# uart_rs232_adapter.net
KiCad netlist of a schematic drawn in EAGLE
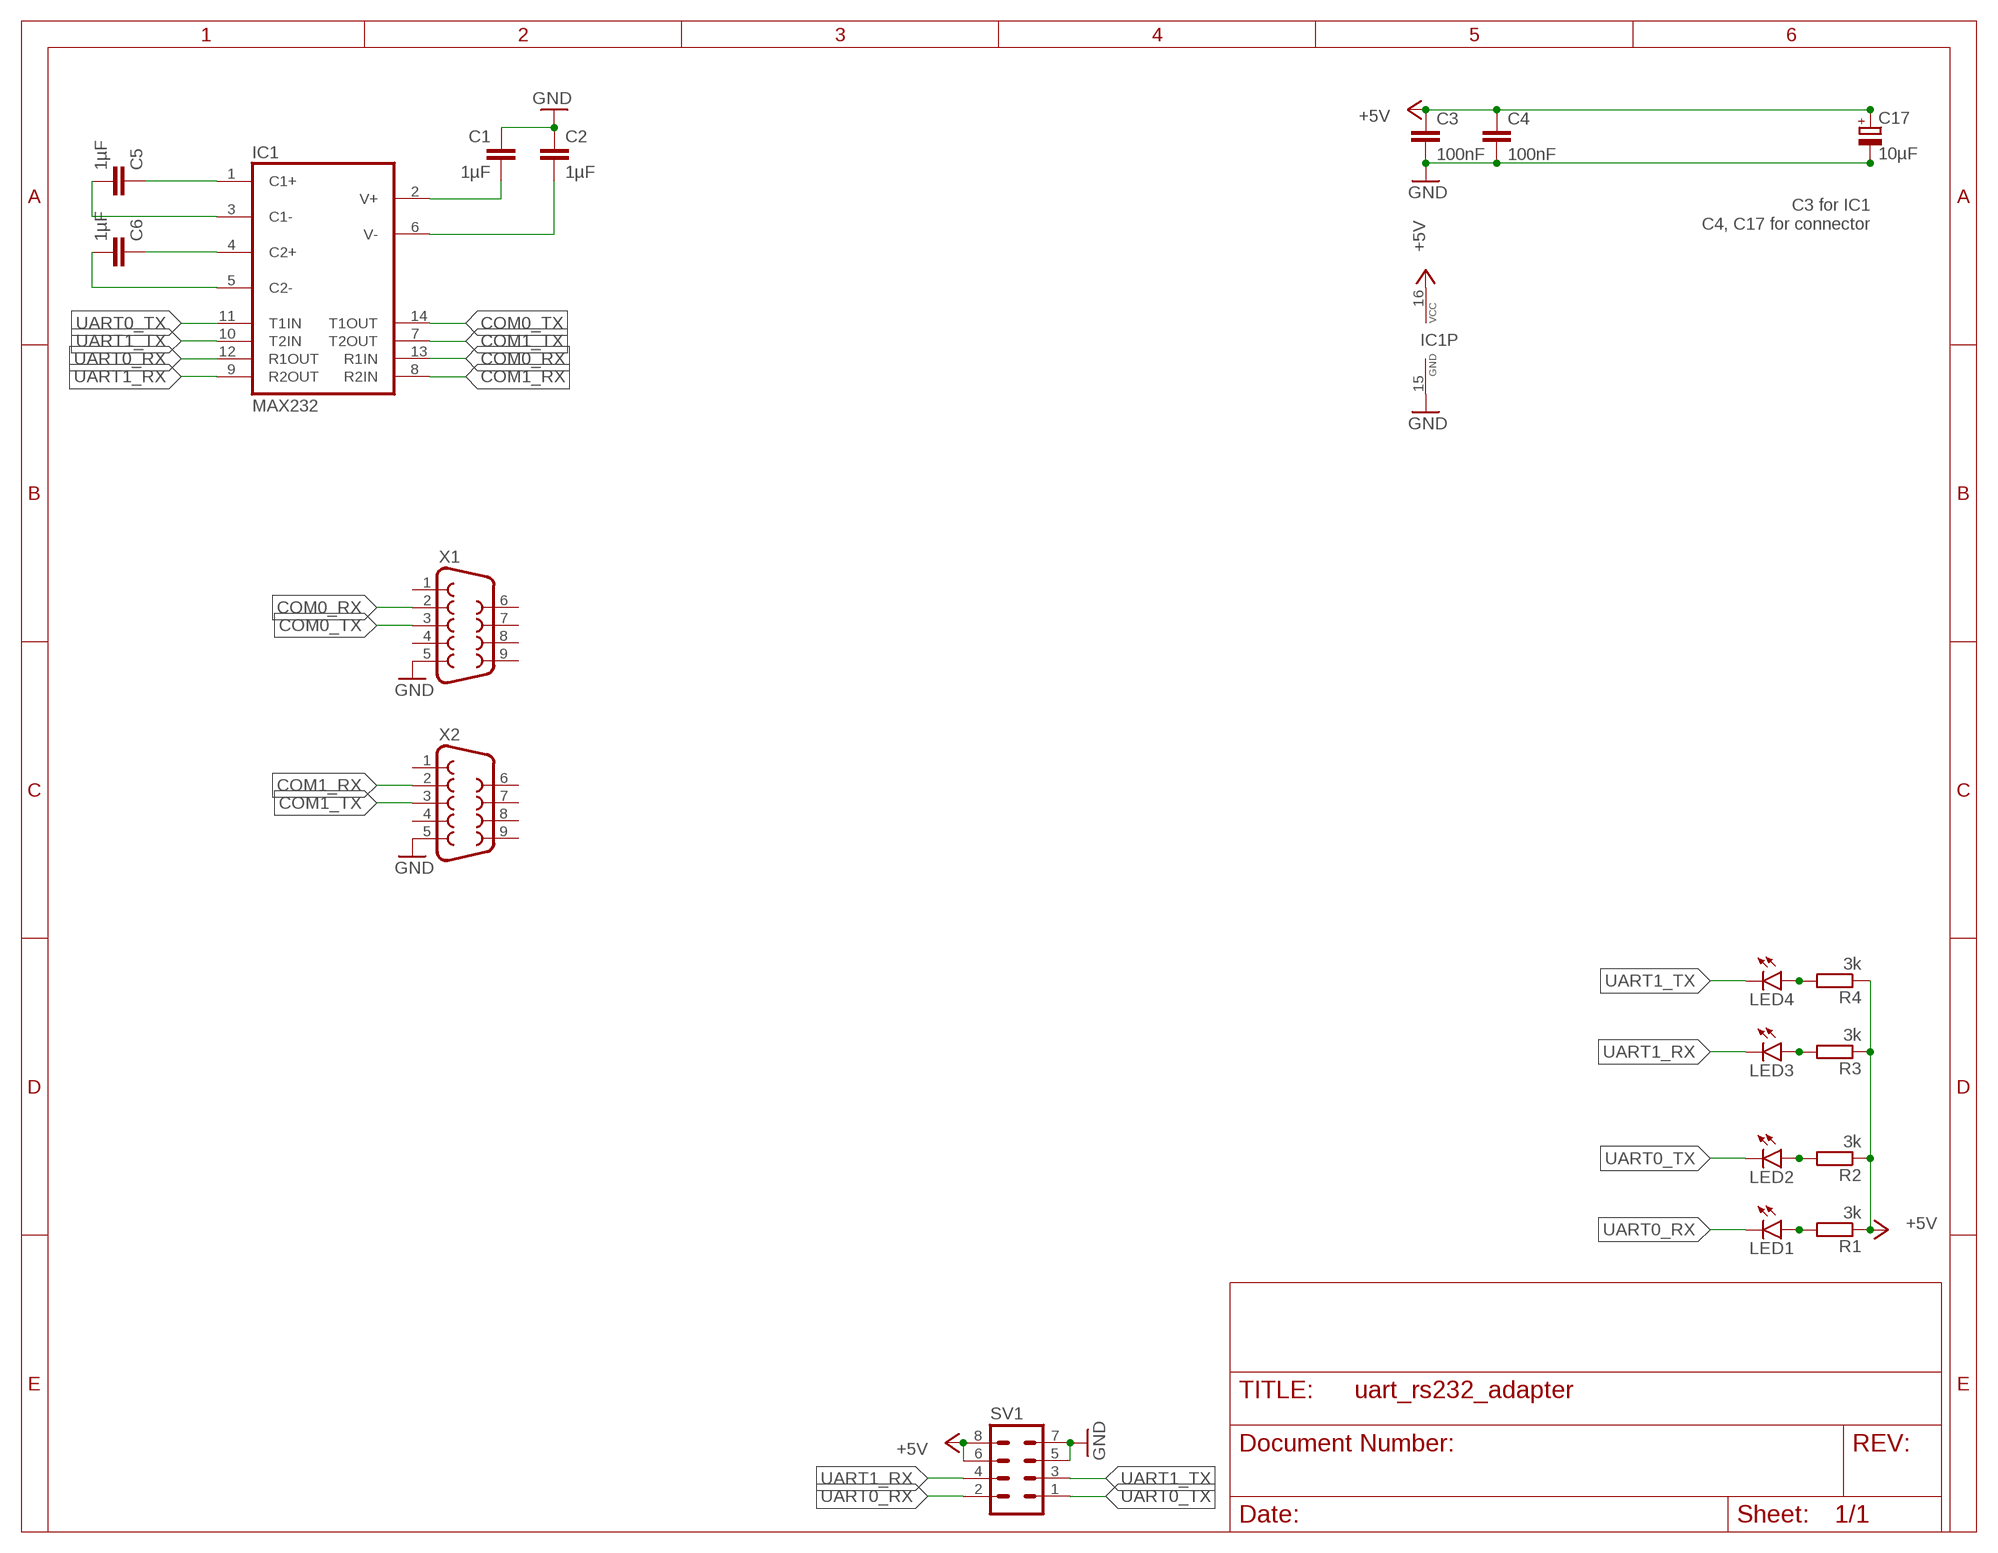
[diagram p0: schematic, sheet 1]

(export (version "E")
  (design (tool "Eeschema 10.0.6"))
  (components
    (comp (ref "C1")
      (value "1µF")
      (footprint "eagle-import:C0805")
      (libsource (lib "eagle-import") (part "C-EUC0805"))
    )
    (comp (ref "C2")
      (value "1µF")
      (footprint "eagle-import:C0805")
      (libsource (lib "eagle-import") (part "C-EUC0805"))
    )
    (comp (ref "C3")
      (value "100nF")
      (footprint "eagle-import:C0805")
      (libsource (lib "eagle-import") (part "C-EUC0805"))
    )
    (comp (ref "C4")
      (value "100nF")
      (footprint "eagle-import:C0805")
      (libsource (lib "eagle-import") (part "C-EUC0805"))
    )
    (comp (ref "C5")
      (value "1µF")
      (footprint "eagle-import:C0805")
      (libsource (lib "eagle-import") (part "C-EUC0805"))
    )
    (comp (ref "C6")
      (value "1µF")
      (footprint "eagle-import:C0805")
      (libsource (lib "eagle-import") (part "C-EUC0805"))
    )
    (comp (ref "C17")
      (value "10µF")
      (footprint "eagle-import:SMC_B")
      (libsource (lib "eagle-import") (part "CPOL-EUSMCB"))
    )
    (comp (ref "IC1")
      (value "MAX232")
      (footprint "eagle-import:DIL16")
      (fields (field (name "MF") "MAXIM") (field (name "MPN") "MAX232ACPE+"))
      (libsource (lib "eagle-import") (part "MAX232"))
    )
    (comp (ref "LED1")
      (value "LEDCHIPLED_1206")
      (footprint "eagle-import:CHIPLED_1206")
      (libsource (lib "eagle-import") (part "LEDCHIPLED_1206"))
    )
    (comp (ref "LED2")
      (value "LEDCHIPLED_1206")
      (footprint "eagle-import:CHIPLED_1206")
      (libsource (lib "eagle-import") (part "LEDCHIPLED_1206"))
    )
    (comp (ref "LED3")
      (value "LEDCHIPLED_1206")
      (footprint "eagle-import:CHIPLED_1206")
      (libsource (lib "eagle-import") (part "LEDCHIPLED_1206"))
    )
    (comp (ref "LED4")
      (value "LEDCHIPLED_1206")
      (footprint "eagle-import:CHIPLED_1206")
      (libsource (lib "eagle-import") (part "LEDCHIPLED_1206"))
    )
    (comp (ref "R1")
      (value "3k")
      (footprint "eagle-import:R2012")
      (libsource (lib "eagle-import") (part "R-EU_R2012"))
    )
    (comp (ref "R2")
      (value "3k")
      (footprint "eagle-import:R2012")
      (libsource (lib "eagle-import") (part "R-EU_R2012"))
    )
    (comp (ref "R3")
      (value "3k")
      (footprint "eagle-import:R2012")
      (libsource (lib "eagle-import") (part "R-EU_R2012"))
    )
    (comp (ref "R4")
      (value "3k")
      (footprint "eagle-import:R2012")
      (libsource (lib "eagle-import") (part "R-EU_R2012"))
    )
    (comp (ref "SV1")
      (value "MA04-2")
      (footprint "eagle-import:MA04-2")
      (libsource (lib "eagle-import") (part "MA04-2"))
    )
    (comp (ref "X1")
      (value "F09HP")
      (footprint "eagle-import:F09HP")
      (libsource (lib "eagle-import") (part "F09HP"))
    )
    (comp (ref "X2")
      (value "F09HP")
      (footprint "eagle-import:F09HP")
      (libsource (lib "eagle-import") (part "F09HP"))
    )
  )
  (nets
    (net (code "1") (name "+5V") (class "Default")
      (node (ref "C17") (pin "+") (pinfunction "+_+") (pintype "passive"))
      (node (ref "C3") (pin "1") (pinfunction "1_1") (pintype "passive"))
      (node (ref "C4") (pin "1") (pinfunction "1_1") (pintype "passive"))
      (node (ref "IC1") (pin "16") (pinfunction "VCC_16") (pintype "power_in"))
      (node (ref "R1") (pin "1") (pinfunction "1_1") (pintype "passive"))
      (node (ref "R2") (pin "1") (pinfunction "1_1") (pintype "passive"))
      (node (ref "R3") (pin "1") (pinfunction "1_1") (pintype "passive"))
      (node (ref "R4") (pin "1") (pinfunction "1_1") (pintype "passive"))
      (node (ref "SV1") (pin "6") (pinfunction "6_6") (pintype "passive"))
      (node (ref "SV1") (pin "8") (pinfunction "8_8") (pintype "passive"))
    )
    (net (code "2") (name "COM0_RX") (class "Default")
      (node (ref "IC1") (pin "13") (pinfunction "R1IN_13") (pintype "input"))
      (node (ref "X1") (pin "2") (pinfunction "2_2") (pintype "passive"))
    )
    (net (code "3") (name "COM0_TX") (class "Default")
      (node (ref "IC1") (pin "14") (pinfunction "T1OUT_14") (pintype "output"))
      (node (ref "X1") (pin "3") (pinfunction "3_3") (pintype "passive"))
    )
    (net (code "4") (name "COM1_RX") (class "Default")
      (node (ref "IC1") (pin "8") (pinfunction "R2IN_8") (pintype "input"))
      (node (ref "X2") (pin "2") (pinfunction "2_2") (pintype "passive"))
    )
    (net (code "5") (name "COM1_TX") (class "Default")
      (node (ref "IC1") (pin "7") (pinfunction "T2OUT_7") (pintype "output"))
      (node (ref "X2") (pin "3") (pinfunction "3_3") (pintype "passive"))
    )
    (net (code "6") (name "GND") (class "Default")
      (node (ref "C1") (pin "1") (pinfunction "1_1") (pintype "passive"))
      (node (ref "C17") (pin "-") (pinfunction "-_-") (pintype "passive"))
      (node (ref "C2") (pin "1") (pinfunction "1_1") (pintype "passive"))
      (node (ref "C3") (pin "2") (pinfunction "2_2") (pintype "passive"))
      (node (ref "C4") (pin "2") (pinfunction "2_2") (pintype "passive"))
      (node (ref "IC1") (pin "15") (pinfunction "GND_15") (pintype "power_in"))
      (node (ref "SV1") (pin "5") (pinfunction "5_5") (pintype "passive"))
      (node (ref "SV1") (pin "7") (pinfunction "7_7") (pintype "passive"))
      (node (ref "X1") (pin "5") (pinfunction "5_5") (pintype "passive"))
      (node (ref "X2") (pin "5") (pinfunction "5_5") (pintype "passive"))
    )
    (net (code "7") (name "Net-(IC1A-C1+)") (class "Default")
      (node (ref "C5") (pin "1") (pinfunction "1_1") (pintype "passive"))
      (node (ref "IC1") (pin "1") (pinfunction "C1+_1") (pintype "bidirectional"))
    )
    (net (code "8") (name "Net-(IC1A-C1-)") (class "Default")
      (node (ref "C5") (pin "2") (pinfunction "2_2") (pintype "passive"))
      (node (ref "IC1") (pin "3") (pinfunction "C1-_3") (pintype "bidirectional"))
    )
    (net (code "9") (name "Net-(IC1A-C2+)") (class "Default")
      (node (ref "C6") (pin "1") (pinfunction "1_1") (pintype "passive"))
      (node (ref "IC1") (pin "4") (pinfunction "C2+_4") (pintype "bidirectional"))
    )
    (net (code "10") (name "Net-(IC1A-C2-)") (class "Default")
      (node (ref "C6") (pin "2") (pinfunction "2_2") (pintype "passive"))
      (node (ref "IC1") (pin "5") (pinfunction "C2-_5") (pintype "bidirectional"))
    )
    (net (code "11") (name "Net-(IC1A-V+)") (class "Default")
      (node (ref "C1") (pin "2") (pinfunction "2_2") (pintype "passive"))
      (node (ref "IC1") (pin "2") (pinfunction "V+_2") (pintype "bidirectional"))
    )
    (net (code "12") (name "Net-(IC1A-V-)") (class "Default")
      (node (ref "C2") (pin "2") (pinfunction "2_2") (pintype "passive"))
      (node (ref "IC1") (pin "6") (pinfunction "V-_6") (pintype "bidirectional"))
    )
    (net (code "13") (name "Net-(LED1-PadA)") (class "Default")
      (node (ref "LED1") (pin "A") (pinfunction "A_A") (pintype "passive"))
      (node (ref "R1") (pin "2") (pinfunction "2_2") (pintype "passive"))
    )
    (net (code "14") (name "Net-(LED2-PadA)") (class "Default")
      (node (ref "LED2") (pin "A") (pinfunction "A_A") (pintype "passive"))
      (node (ref "R2") (pin "2") (pinfunction "2_2") (pintype "passive"))
    )
    (net (code "15") (name "Net-(LED3-PadA)") (class "Default")
      (node (ref "LED3") (pin "A") (pinfunction "A_A") (pintype "passive"))
      (node (ref "R3") (pin "2") (pinfunction "2_2") (pintype "passive"))
    )
    (net (code "16") (name "Net-(LED4-PadA)") (class "Default")
      (node (ref "LED4") (pin "A") (pinfunction "A_A") (pintype "passive"))
      (node (ref "R4") (pin "2") (pinfunction "2_2") (pintype "passive"))
    )
    (net (code "17") (name "UART0_RX") (class "Default")
      (node (ref "IC1") (pin "12") (pinfunction "R1OUT_12") (pintype "output"))
      (node (ref "LED1") (pin "C") (pinfunction "C_C") (pintype "passive"))
      (node (ref "SV1") (pin "2") (pinfunction "2_2") (pintype "passive"))
    )
    (net (code "18") (name "UART0_TX") (class "Default")
      (node (ref "IC1") (pin "11") (pinfunction "T1IN_11") (pintype "input"))
      (node (ref "LED2") (pin "C") (pinfunction "C_C") (pintype "passive"))
      (node (ref "SV1") (pin "1") (pinfunction "1_1") (pintype "passive"))
    )
    (net (code "19") (name "UART1_RX") (class "Default")
      (node (ref "IC1") (pin "9") (pinfunction "R2OUT_9") (pintype "output"))
      (node (ref "LED3") (pin "C") (pinfunction "C_C") (pintype "passive"))
      (node (ref "SV1") (pin "4") (pinfunction "4_4") (pintype "passive"))
    )
    (net (code "20") (name "UART1_TX") (class "Default")
      (node (ref "IC1") (pin "10") (pinfunction "T2IN_10") (pintype "input"))
      (node (ref "LED4") (pin "C") (pinfunction "C_C") (pintype "passive"))
      (node (ref "SV1") (pin "3") (pinfunction "3_3") (pintype "passive"))
    )
    (net (code "21") (name "unconnected-(X1-Pad1)") (class "Default")
      (node (ref "X1") (pin "1") (pinfunction "1_1") (pintype "passive"))
    )
    (net (code "22") (name "unconnected-(X1-Pad4)") (class "Default")
      (node (ref "X1") (pin "4") (pinfunction "4_4") (pintype "passive"))
    )
    (net (code "23") (name "unconnected-(X1-Pad6)") (class "Default")
      (node (ref "X1") (pin "6") (pinfunction "6_6") (pintype "passive"))
    )
    (net (code "24") (name "unconnected-(X1-Pad7)") (class "Default")
      (node (ref "X1") (pin "7") (pinfunction "7_7") (pintype "passive"))
    )
    (net (code "25") (name "unconnected-(X1-Pad8)") (class "Default")
      (node (ref "X1") (pin "8") (pinfunction "8_8") (pintype "passive"))
    )
    (net (code "26") (name "unconnected-(X1-Pad9)") (class "Default")
      (node (ref "X1") (pin "9") (pinfunction "9_9") (pintype "passive"))
    )
    (net (code "27") (name "unconnected-(X2-Pad1)") (class "Default")
      (node (ref "X2") (pin "1") (pinfunction "1_1") (pintype "passive"))
    )
    (net (code "28") (name "unconnected-(X2-Pad4)") (class "Default")
      (node (ref "X2") (pin "4") (pinfunction "4_4") (pintype "passive"))
    )
    (net (code "29") (name "unconnected-(X2-Pad6)") (class "Default")
      (node (ref "X2") (pin "6") (pinfunction "6_6") (pintype "passive"))
    )
    (net (code "30") (name "unconnected-(X2-Pad7)") (class "Default")
      (node (ref "X2") (pin "7") (pinfunction "7_7") (pintype "passive"))
    )
    (net (code "31") (name "unconnected-(X2-Pad8)") (class "Default")
      (node (ref "X2") (pin "8") (pinfunction "8_8") (pintype "passive"))
    )
    (net (code "32") (name "unconnected-(X2-Pad9)") (class "Default")
      (node (ref "X2") (pin "9") (pinfunction "9_9") (pintype "passive"))
    )
  )
)
